# Power.net
KiCad netlist of a schematic drawn in Altium Designer
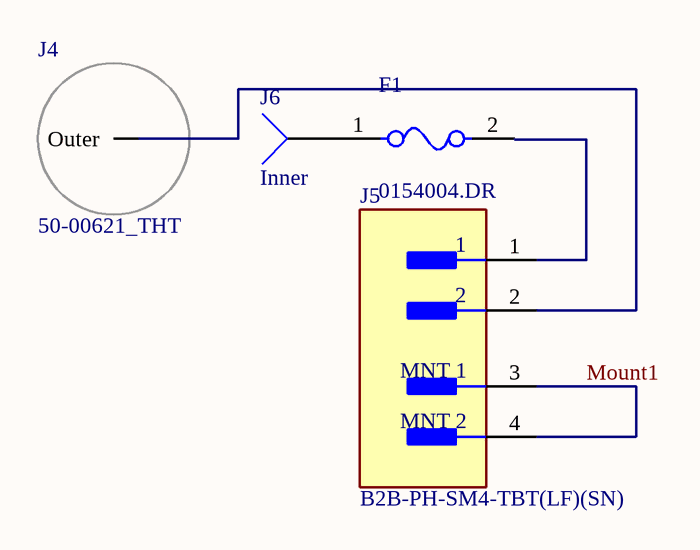
[diagram p0: Power.SchDoc]

(export (version "E")
  (design (tool "Eeschema 10.0.6"))
  (components
    (comp (ref "F1")
      (value "0154004.DR")
      (footprint "FP-0154-MFG")
      (description "FUSE BRD MNT 4A 125VAC/VDC 2SMD")
      (fields
        (field (name "MANUFACTURER") "Littelfuse")
        (field (name "OCTOPART") "https://octopart.com/0154004.dr-littelfuse-565861")
      )
      (libsource (lib "Altium Content Vault") (part "5bcf9b9f640e542cf0359d10258e979"))
    )
    (comp (ref "J4")
      (value "50-00621_THT")
      (footprint "50-00621_THT")
      (libsource (lib "MiniDin") (part "50-00621"))
    )
    (comp (ref "J5")
      (value "B2B-PH-SM4-TBT(LF)(SN)")
      (footprint "FP-B2B-PH-SM4-TBT_LF_SN-MFG")
      (description "CONN HEADER SMD 2POS 2MM")
      (fields
        (field (name "OCTOPART") "https://octopart.com/b2b-ph-sm4-tbt%28lf%29%28sn%29-jst-7877930")
        (field (name "MANUFACTURER") "JST")
      )
      (libsource (lib "Altium Content Vault") (part "56ec3178a87b3978bdc1b3682cd516a"))
    )
    (comp (ref "J6")
      (value "Inner")
      (footprint "PIN1")
      (description "Socket")
      (fields (field (name "PUBLISHER") "Altium Limited"))
      (libsource (lib "Miscellaneous Connectors") (part "Socket"))
    )
  )
  (nets
    (net (code "1") (name "/Mount1") (class "Default")
      (node (ref "J5") (pin "3") (pinfunction "MNT_1_3") (pintype "passive"))
      (node (ref "J5") (pin "4") (pinfunction "MNT_2_4") (pintype "passive"))
    )
    (net (code "2") (name "Net-(F1-Pad1)") (class "Default")
      (node (ref "F1") (pin "1") (pinfunction "1_1") (pintype "passive"))
      (node (ref "J6") (pin "1") (pinfunction "1_1") (pintype "passive"))
    )
    (net (code "3") (name "Net-(F1-Pad2)") (class "Default")
      (node (ref "F1") (pin "2") (pinfunction "2_2") (pintype "passive"))
      (node (ref "J5") (pin "1") (pinfunction "1_1") (pintype "passive"))
    )
    (net (code "4") (name "Net-(J4-Outer)") (class "Default")
      (node (ref "J4") (pin "1") (pinfunction "Outer_1") (pintype "passive"))
      (node (ref "J5") (pin "2") (pinfunction "2_2") (pintype "passive"))
    )
  )
)
